# Power_Circuit.net
KiCad netlist of a schematic drawn in Altium Designer
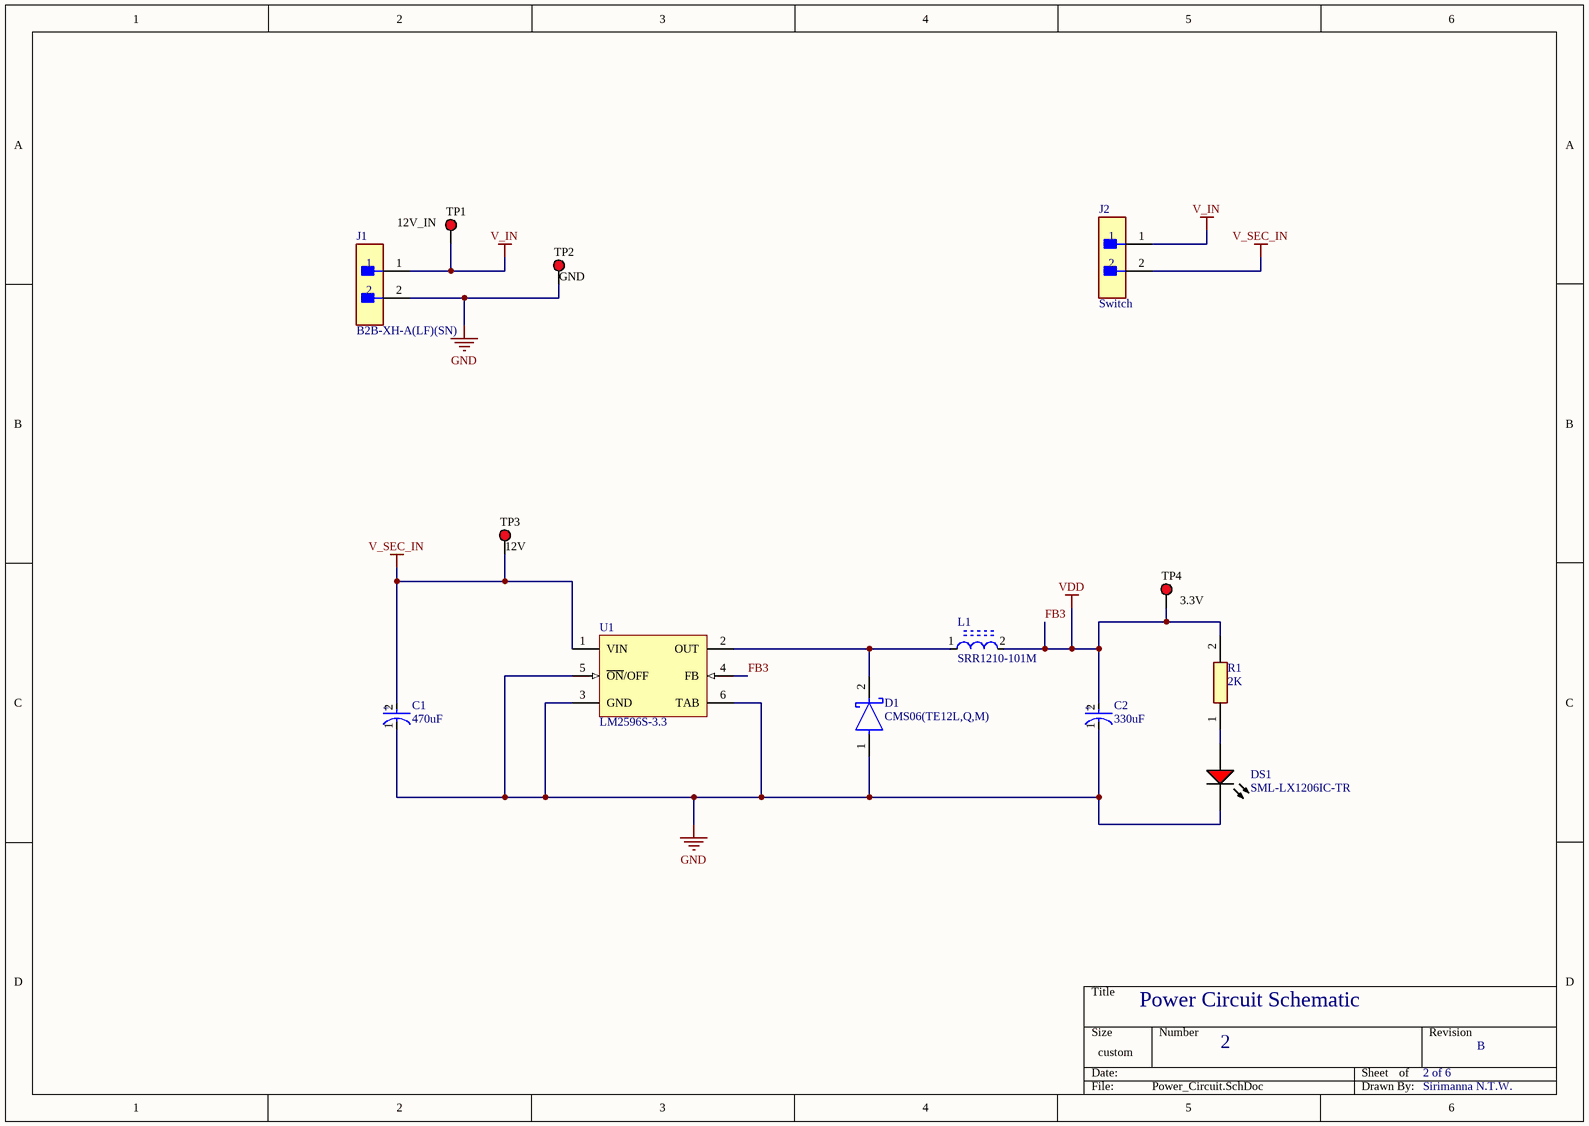
[diagram p0: Power_Circuit.SchDoc]

(export (version "E")
  (design (tool "Eeschema 10.0.6"))
  (components
    (comp (ref "C1")
      (value "470uF")
      (footprint "FP-ZAG-MFG")
      (description "CAP ALUM POLY HYB 100UF 50V SMD")
      (fields (field (name "VOLTAGE") "50V") (field (name "MANUFACTURER") "Panasonic"))
      (libsource (lib "Altium Content Vault") (part "cf48714ba7e38822c1575c7ec0b6d1f"))
    )
    (comp (ref "C2")
      (value "330uF")
      (footprint "FP-FKG-MFG")
      (description "CAP ALUM 330UF 20% 35V SMD")
      (fields (field (name "VOLTAGE") "35V") (field (name "TOLERANCE") "20%"))
      (libsource (lib "Altium Content Vault") (part "203bc49f2ac43e59fd269a8c329ed05"))
    )
    (comp (ref "D1")
      (value "CMS06(TE12L,Q,M)")
      (footprint "FP-M-FLAT-MFG")
      (description "DIODE SCHOTTKY 30V 2A MFLAT")
      (libsource (lib "Altium Content Vault") (part "360ad2f4ac25a952324d13796385471"))
    )
    (comp (ref "DS1")
      (value "SML-LX1206IC-TR")
      (footprint "LUMX-SML-LX1206IC_V")
      (description "LED Red, 65 mW, -40 to 85 degC, 2-Pin SMD, RoHS, Tape and Reel")
      (fields (field (name "MANUFACTURER") "Lumex"))
      (libsource (lib "Altium Content Vault") (part "LED-RED-AK-2"))
    )
    (comp (ref "J1")
      (value "B2B-XH-A(LF)(SN)")
      (footprint "FP-B2B-XH-A_LF_SN-MFG")
      (description "CONN HEADER VERT 2POS 2.5MM")
      (libsource (lib "Altium Content Vault") (part "3bc925449376181038e59eaffc5286c"))
    )
    (comp (ref "J2")
      (value "Switch")
      (footprint "FP-B2B-XH-A_LF_SN-MFG")
      (description "To power Switch")
      (libsource (lib "Altium Content Vault") (part "3bc925449376181038e59eaffc5286c"))
    )
    (comp (ref "L1")
      (value "SRR1210-101M")
      (footprint "FP-SRR1210-MFG")
      (description "FIXED IND 100UH 2.5A 135MOHM SMD")
      (fields (field (name "TOLERANCE") "20%"))
      (libsource (lib "Altium Content Vault") (part "b0910935bcc1a60cf5c5c74d6a451c2"))
    )
    (comp (ref "R1")
      (value "2K")
      (footprint "SamacSys:RESC3216X75N")
      (description "Resistor")
      (fields
        (field (name "MANUFACTURER_PART_NUMBER") "CR1206-FX-1022ELF")
        (field (name "MOUSER PART NUMBER") "652-CR1206FX-1022ELF")
      )
      (libsource (lib "*") (part "CR1206-FX-1022ELF"))
    )
    (comp (ref "TP1")
      (value "12V_IN")
      (footprint "KSTN-5010_V")
      (description "Test Point, Red, Through Hole, RoHS, Bulk")
      (fields (field (name "MANUFACTURER") "Keystone"))
      (libsource (lib "Altium Content Vault") (part "TESTPOINT_RED"))
    )
    (comp (ref "TP2")
      (value "GND")
      (footprint "KSTN-5010_V")
      (description "Test Point, Red, Through Hole, RoHS, Bulk")
      (fields (field (name "MANUFACTURER") "Keystone"))
      (libsource (lib "Altium Content Vault") (part "TESTPOINT_RED"))
    )
    (comp (ref "TP3")
      (value "12V")
      (footprint "KSTN-5010_V")
      (description "Test Point, Red, Through Hole, RoHS, Bulk")
      (fields (field (name "MANUFACTURER") "Keystone"))
      (libsource (lib "Altium Content Vault") (part "TESTPOINT_RED"))
    )
    (comp (ref "TP4")
      (value "3.3V")
      (footprint "KSTN-5010_V")
      (description "Test Point, Red, Through Hole, RoHS, Bulk")
      (fields (field (name "MANUFACTURER") "Keystone"))
      (libsource (lib "Altium Content Vault") (part "TESTPOINT_RED"))
    )
    (comp (ref "U1")
      (value "LM2596S-3.3")
      (footprint "KTT0005B_N")
      (description "SIMPLE SWITCHER® Power Converter 150 KHz 3A Step-Down Voltage Regulator, 5-pin TO-263")
      (fields (field (name "MANUFACTURER") "Texas Instruments"))
      (libsource (lib "Altium Content Vault") (part "PM-REG-LM2575HVS-12"))
    )
  )
  (nets
    (net (code "1") (name "GND") (class "Default")
      (node (ref "C1") (pin "1") (pinfunction "C_1") (pintype "passive"))
      (node (ref "C2") (pin "1") (pinfunction "C_1") (pintype "passive"))
      (node (ref "D1") (pin "1") (pinfunction "A_1") (pintype "passive"))
      (node (ref "DS1") (pin "2") (pinfunction "K_2") (pintype "passive"))
      (node (ref "J1") (pin "2") (pinfunction "2_2") (pintype "passive"))
      (node (ref "TP2") (pin "1") (pinfunction "1_1") (pintype "passive"))
      (node (ref "U1") (pin "3") (pinfunction "GND_3") (pintype "power_in"))
      (node (ref "U1") (pin "5") (pinfunction "~{ON}/OFF_5") (pintype "input"))
      (node (ref "U1") (pin "6") (pinfunction "TAB_6") (pintype "power_in"))
    )
    (net (code "2") (name "Net-(D1-C)") (class "Default")
      (node (ref "D1") (pin "2") (pinfunction "C_2") (pintype "passive"))
      (node (ref "L1") (pin "1") (pinfunction "1_1") (pintype "passive"))
      (node (ref "U1") (pin "2") (pinfunction "OUT_2") (pintype "power_in"))
    )
    (net (code "3") (name "Net-(DS1-A)") (class "Default")
      (node (ref "DS1") (pin "1") (pinfunction "A_1") (pintype "passive"))
      (node (ref "R1") (pin "1") (pinfunction "1_1") (pintype "passive"))
    )
    (net (code "4") (name "VDD") (class "Default")
      (node (ref "C2") (pin "2") (pinfunction "A_2") (pintype "passive"))
      (node (ref "L1") (pin "2") (pinfunction "2_2") (pintype "passive"))
      (node (ref "R1") (pin "2") (pinfunction "2_2") (pintype "passive"))
      (node (ref "TP4") (pin "1") (pinfunction "1_1") (pintype "passive"))
      (node (ref "U1") (pin "4") (pinfunction "FB_4") (pintype "input"))
    )
    (net (code "5") (name "V_IN") (class "Default")
      (node (ref "J1") (pin "1") (pinfunction "1_1") (pintype "passive"))
      (node (ref "J2") (pin "1") (pinfunction "1_1") (pintype "passive"))
      (node (ref "TP1") (pin "1") (pinfunction "1_1") (pintype "passive"))
    )
    (net (code "6") (name "V_SEC_IN") (class "Default")
      (node (ref "C1") (pin "2") (pinfunction "A_2") (pintype "passive"))
      (node (ref "J2") (pin "2") (pinfunction "2_2") (pintype "passive"))
      (node (ref "TP3") (pin "1") (pinfunction "1_1") (pintype "passive"))
      (node (ref "U1") (pin "1") (pinfunction "VIN_1") (pintype "power_in"))
    )
  )
)
